# POWER.net
KiCad netlist of a schematic drawn in Altium Designer
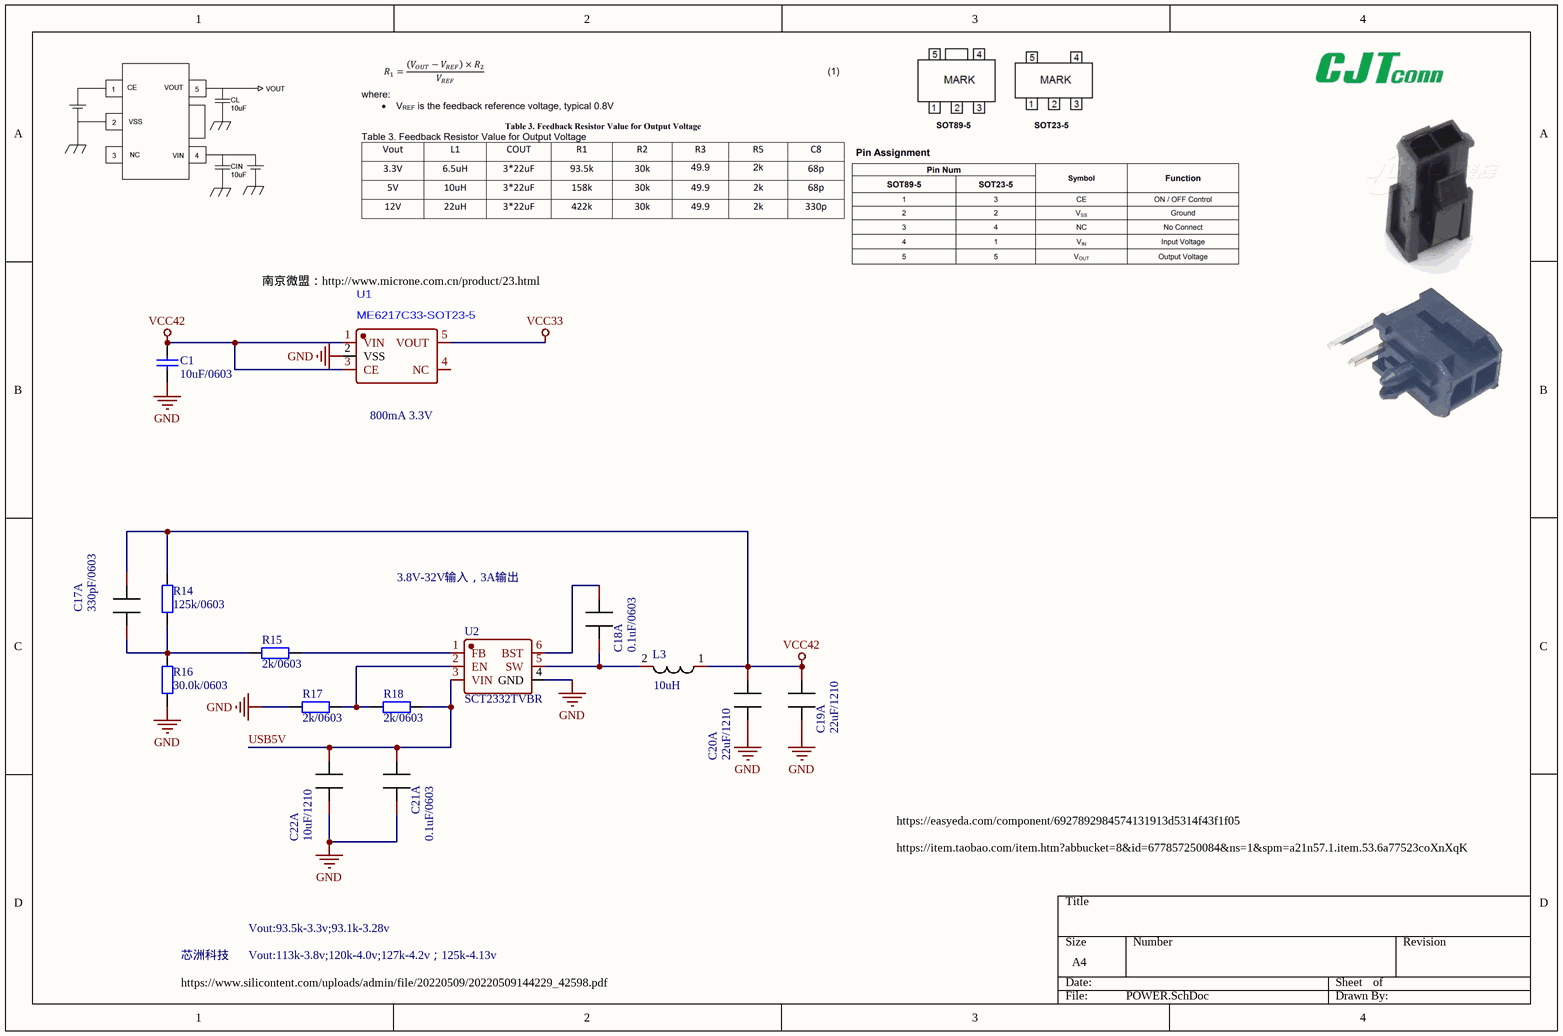
[diagram p0: POWER.SchDoc]

(export (version "E")
  (design (tool "Eeschema 10.0.6"))
  (components
    (comp (ref "C1")
      (value "10uF/0603")
      (footprint "CAP0603")
      (description "Capacitor (Semiconductor SIM Model)")
      (fields (field (name "PUBLISHER") "Altium Limited"))
      (libsource (lib "Miscellaneous Devices") (part "Cap Semi"))
    )
    (comp (ref "C17")
      (value "330pF/0603")
      (footprint "CAP0603")
      (description "SURFACE MOUNT CAPACITOR 0.031 X 0.061 INCHES")
      (libsource (lib "altium-import") (part "root_0_CAP0603_"))
    )
    (comp (ref "C18")
      (value "0.1uF/0603")
      (footprint "CAP0603")
      (description "SURFACE MOUNT CAPACITOR 0.031 X 0.061 INCHES")
      (libsource (lib "altium-import") (part "root_0_CAP0603_"))
    )
    (comp (ref "C19")
      (value "22uF/1210")
      (footprint "CAP0603")
      (description "SURFACE MOUNT CAPACITOR 0.031 X 0.061 INCHES")
      (libsource (lib "altium-import") (part "root_0_CAP0603_"))
    )
    (comp (ref "C20")
      (value "22uF/1210")
      (footprint "CAP1210-CAPC3225X140N")
      (description "SURFACE MOUNT CAPACITOR 0.031 X 0.061 INCHES")
      (libsource (lib "altium-import") (part "root_0_CAP0603_"))
    )
    (comp (ref "C21")
      (value "0.1uF/0603")
      (footprint "CAP0603")
      (description "SURFACE MOUNT CAPACITOR 0.031 X 0.061 INCHES")
      (libsource (lib "altium-import") (part "root_0_CAP0603_"))
    )
    (comp (ref "C22")
      (value "10uF/1210")
      (footprint "CAP1210-CAPC3225X140N")
      (description "SURFACE MOUNT CAPACITOR 0.031 X 0.061 INCHES")
      (libsource (lib "altium-import") (part "root_0_CAP0603_"))
    )
    (comp (ref "L3")
      (value "10uH")
      (footprint "IND-SMD_L4.7-W4.7-6.5uH")
      (description "0503贴片电感")
      (libsource (lib "altium-import") (part "root_2_IND-MOLDED_"))
    )
    (comp (ref "R14")
      (value "125k/0603")
      (footprint "RES0603")
      (description "Resistor")
      (fields (field (name "PUBLISHER") "Altium Limited"))
      (libsource (lib "") (part "Res2_1"))
    )
    (comp (ref "R15")
      (value "2k/0603")
      (footprint "RES0603")
      (description "Resistor")
      (fields (field (name "PUBLISHER") "Altium Limited"))
      (libsource (lib "Miscellaneous Devices") (part "Res2"))
    )
    (comp (ref "R16")
      (value "30.0k/0603")
      (footprint "RES0603")
      (description "Resistor")
      (fields (field (name "PUBLISHER") "Altium Limited"))
      (libsource (lib "") (part "Res2_1"))
    )
    (comp (ref "R17")
      (value "2k/0603")
      (footprint "RES0603")
      (description "Resistor")
      (fields (field (name "PUBLISHER") "Altium Limited"))
      (libsource (lib "Miscellaneous Devices") (part "Res2"))
    )
    (comp (ref "R18")
      (value "2k/0603")
      (footprint "RES0603")
      (description "Resistor")
      (fields (field (name "PUBLISHER") "Altium Limited"))
      (libsource (lib "Miscellaneous Devices") (part "Res2"))
    )
    (comp (ref "U1")
      (value "ME6217C33-SOT23-5")
      (footprint "ME6217C33-SOT23-5")
      (description "4.2v-3.3v LDO")
      (libsource (lib "altium-import") (part "root_0_ME6217C33M5G_"))
    )
    (comp (ref "U2")
      (value "SCT2332TVBR")
      (footprint "SCT2332TVBR-TSOT23-6")
      (description "3.8V-32V Vin, 3A Synchronous Step-down DCDC Converter")
      (libsource (lib "ChargingPile") (part "SCT2332TVBR"))
    )
  )
  (nets
    (net (code "1") (name "/USB5V") (class "Default")
      (node (ref "C21") (pin "1") (pintype "passive"))
      (node (ref "C22") (pin "1") (pintype "passive"))
      (node (ref "R18") (pin "1") (pinfunction "1_1") (pintype "passive"))
      (node (ref "U2") (pin "3") (pinfunction "VIN_3") (pintype "passive"))
    )
    (net (code "2") (name "GND") (class "Default")
      (node (ref "C1") (pin "1") (pinfunction "1_1") (pintype "passive"))
      (node (ref "C19") (pin "2") (pintype "passive"))
      (node (ref "C20") (pin "2") (pintype "passive"))
      (node (ref "C21") (pin "2") (pintype "passive"))
      (node (ref "C22") (pin "2") (pintype "passive"))
      (node (ref "R16") (pin "2") (pinfunction "2_2") (pintype "passive"))
      (node (ref "R17") (pin "2") (pinfunction "2_2") (pintype "passive"))
      (node (ref "U1") (pin "2") (pinfunction "VSS_2") (pintype "passive"))
      (node (ref "U2") (pin "4") (pinfunction "GND_4") (pintype "passive"))
    )
    (net (code "3") (name "Net-(C17-Pad2)") (class "Default")
      (node (ref "C17") (pin "2") (pintype "passive"))
      (node (ref "R14") (pin "2") (pinfunction "2_2") (pintype "passive"))
      (node (ref "R15") (pin "2") (pinfunction "2_2") (pintype "passive"))
      (node (ref "R16") (pin "1") (pinfunction "1_1") (pintype "passive"))
    )
    (net (code "4") (name "Net-(U2-BST)") (class "Default")
      (node (ref "C18") (pin "1") (pintype "passive"))
      (node (ref "U2") (pin "6") (pinfunction "BST_6") (pintype "passive"))
    )
    (net (code "5") (name "Net-(U2-EN)") (class "Default")
      (node (ref "R17") (pin "1") (pinfunction "1_1") (pintype "passive"))
      (node (ref "R18") (pin "2") (pinfunction "2_2") (pintype "passive"))
      (node (ref "U2") (pin "2") (pinfunction "EN_2") (pintype "passive"))
    )
    (net (code "6") (name "Net-(U2-FB)") (class "Default")
      (node (ref "R15") (pin "1") (pinfunction "1_1") (pintype "passive"))
      (node (ref "U2") (pin "1") (pinfunction "FB_1") (pintype "passive"))
    )
    (net (code "7") (name "Net-(U2-SW)") (class "Default")
      (node (ref "C18") (pin "2") (pintype "passive"))
      (node (ref "L3") (pin "2") (pintype "passive"))
      (node (ref "U2") (pin "5") (pinfunction "SW_5") (pintype "passive"))
    )
    (net (code "8") (name "VCC33") (class "Default")
      (node (ref "U1") (pin "5") (pinfunction "VOUT_5") (pintype "passive"))
    )
    (net (code "9") (name "VCC42") (class "Default")
      (node (ref "C1") (pin "2") (pinfunction "2_2") (pintype "passive"))
      (node (ref "C17") (pin "1") (pintype "passive"))
      (node (ref "C19") (pin "1") (pintype "passive"))
      (node (ref "C20") (pin "1") (pintype "passive"))
      (node (ref "L3") (pin "1") (pintype "passive"))
      (node (ref "R14") (pin "1") (pinfunction "1_1") (pintype "passive"))
      (node (ref "U1") (pin "1") (pinfunction "VIN_1") (pintype "passive"))
      (node (ref "U1") (pin "3") (pinfunction "CE_3") (pintype "passive"))
    )
    (net (code "10") (name "unconnected-(U1-NC-Pad4)") (class "Default")
      (node (ref "U1") (pin "4") (pinfunction "NC_4") (pintype "passive"))
    )
  )
)
